# Sheet2.net
KiCad netlist of a schematic drawn in Altium Designer
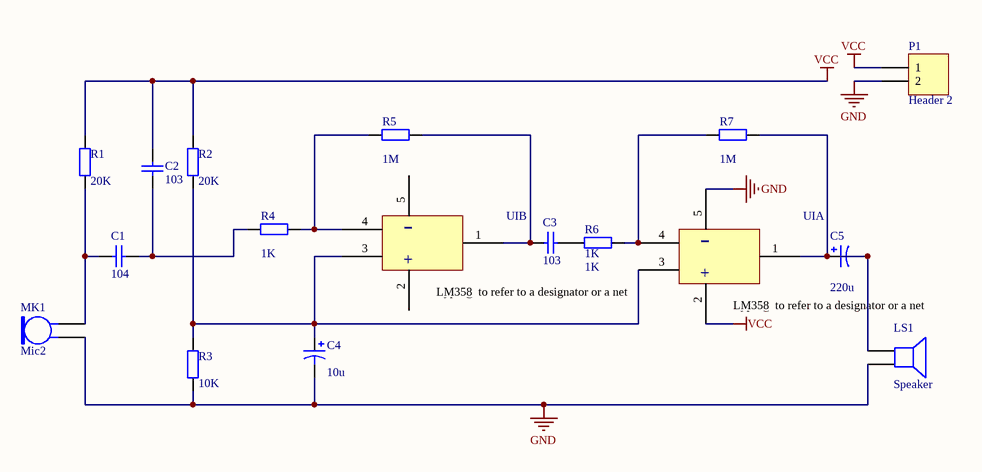
[diagram p0: Sheet2.SchDoc]

(export (version "E")
  (design (tool "Eeschema 10.0.6"))
  (components
    (comp (ref "C1")
      (value "104")
      (footprint "RAD-0.3")
      (description "Capacitor")
      (fields (field (name "PUBLISHER") "Altium Limited"))
      (libsource (lib "Miscellaneous Devices") (part "Cap"))
    )
    (comp (ref "C2")
      (value "103")
      (footprint "RAD-0.3")
      (description "Capacitor")
      (fields (field (name "PUBLISHER") "Altium Limited"))
      (libsource (lib "Miscellaneous Devices") (part "Cap"))
    )
    (comp (ref "C3")
      (value "103")
      (footprint "RAD-0.3")
      (description "Capacitor")
      (fields (field (name "PUBLISHER") "Altium Limited"))
      (libsource (lib "Miscellaneous Devices") (part "Cap"))
    )
    (comp (ref "C4")
      (value "10u")
      (footprint "RB7.6-15")
      (description "Polarized Capacitor (Radial)")
      (fields (field (name "Comment") "Cap Pol1") (field (name "PUBLISHER") "Altium Limited"))
      (libsource (lib "Miscellaneous Devices") (part "Cap Pol1"))
    )
    (comp (ref "C5")
      (value "220u")
      (footprint "RB7.6-15")
      (description "Polarized Capacitor (Radial)")
      (fields (field (name "Comment") "Cap Pol1") (field (name "PUBLISHER") "Altium Limited"))
      (libsource (lib "Miscellaneous Devices") (part "Cap Pol1"))
    )
    (comp (ref "LS1")
      (value "Speaker")
      (footprint "PIN2")
      (description "Loudspeaker")
      (fields (field (name "PUBLISHER") "Altium Limited"))
      (libsource (lib "Miscellaneous Devices") (part "Speaker"))
    )
    (comp (ref "MK1")
      (value "Mic2")
      (footprint "PIN2")
      (description "Microphone")
      (fields (field (name "PUBLISHER") "Altium Limited"))
      (libsource (lib "Miscellaneous Devices") (part "Mic2"))
    )
    (comp (ref "P1")
      (value "Header 2")
      (footprint "HDR1X2")
      (description "Header, 2-Pin")
      (fields (field (name "PUBLISHER") "Altium Limited"))
      (libsource (lib "Miscellaneous Connectors") (part "Header 2"))
    )
    (comp (ref "R1")
      (value "20K")
      (footprint "AXIAL-0.4")
      (description "Resistor")
      (fields (field (name "Comment") "Res2") (field (name "PUBLISHER") "Altium Limited"))
      (libsource (lib "") (part "Res2_1"))
    )
    (comp (ref "R2")
      (value "20K")
      (footprint "AXIAL-0.4")
      (description "Resistor")
      (fields (field (name "Comment") "Res2") (field (name "PUBLISHER") "Altium Limited"))
      (libsource (lib "") (part "Res2_1"))
    )
    (comp (ref "R3")
      (value "10K")
      (footprint "AXIAL-0.4")
      (description "Resistor")
      (fields (field (name "Comment") "Res2") (field (name "PUBLISHER") "Altium Limited"))
      (libsource (lib "") (part "Res2_2"))
    )
    (comp (ref "R4")
      (value "1K")
      (footprint "AXIAL-0.4")
      (description "Resistor")
      (fields (field (name "Comment") "Res2") (field (name "PUBLISHER") "Altium Limited"))
      (libsource (lib "Miscellaneous Devices") (part "Res2"))
    )
    (comp (ref "R5")
      (value "1M")
      (footprint "AXIAL-0.4")
      (description "Resistor")
      (fields (field (name "Comment") "Res2") (field (name "PUBLISHER") "Altium Limited"))
      (libsource (lib "Miscellaneous Devices") (part "Res2"))
    )
    (comp (ref "R6")
      (value "1K")
      (footprint "AXIAL-0.4")
      (description "Resistor")
      (fields (field (name "ALTIUM_VALUE") "1K") (field (name "PUBLISHER") "Altium Limited"))
      (libsource (lib "") (part "Res2_3"))
    )
    (comp (ref "R7")
      (value "1M")
      (footprint "AXIAL-0.4")
      (description "Resistor")
      (fields (field (name "Comment") "Res2") (field (name "PUBLISHER") "Altium Limited"))
      (libsource (lib "") (part "Res2_3"))
    )
    (comp (ref "UIA") (value "双运算放大器") (footprint "LM358") (libsource (lib "1.1Schlib") (part "放大器")))
    (comp (ref "UIB") (value "双运算放大器") (footprint "LM358") (libsource (lib "1.1Schlib") (part "放大器")))
  )
  (nets
    (net (code "1") (name "GND") (class "Default")
      (node (ref "C4") (pin "2") (pinfunction "2_2") (pintype "passive"))
      (node (ref "LS1") (pin "2") (pinfunction "2_2") (pintype "passive"))
      (node (ref "MK1") (pin "1") (pinfunction "1_1") (pintype "passive"))
      (node (ref "P1") (pin "2") (pinfunction "2_2") (pintype "passive"))
      (node (ref "R3") (pin "2") (pinfunction "2_2") (pintype "passive"))
      (node (ref "UIA") (pin "5") (pinfunction "GND_5") (pintype "passive"))
    )
    (net (code "2") (name "Net-(C1-Pad1)") (class "Default")
      (node (ref "C1") (pin "1") (pinfunction "1_1") (pintype "passive"))
      (node (ref "MK1") (pin "2") (pinfunction "2_2") (pintype "passive"))
      (node (ref "R1") (pin "1") (pinfunction "1_1") (pintype "passive"))
    )
    (net (code "3") (name "Net-(C1-Pad2)") (class "Default")
      (node (ref "C1") (pin "2") (pinfunction "2_2") (pintype "passive"))
      (node (ref "C2") (pin "1") (pinfunction "1_1") (pintype "passive"))
      (node (ref "R4") (pin "2") (pinfunction "2_2") (pintype "passive"))
    )
    (net (code "4") (name "Net-(C3-Pad2)") (class "Default")
      (node (ref "C3") (pin "2") (pinfunction "2_2") (pintype "passive"))
      (node (ref "R6") (pin "1") (pinfunction "1_1") (pintype "passive"))
    )
    (net (code "5") (name "Net-(C5-Pad2)") (class "Default")
      (node (ref "C5") (pin "2") (pinfunction "2_2") (pintype "passive"))
      (node (ref "LS1") (pin "1") (pinfunction "1_1") (pintype "passive"))
    )
    (net (code "6") (name "Net-(R4-Pad1)") (class "Default")
      (node (ref "R4") (pin "1") (pinfunction "1_1") (pintype "passive"))
      (node (ref "R5") (pin "2") (pinfunction "2_2") (pintype "passive"))
      (node (ref "UIB") (pin "4") (pintype "passive"))
    )
    (net (code "7") (name "Net-(R6-Pad2)") (class "Default")
      (node (ref "R6") (pin "2") (pinfunction "2_2") (pintype "passive"))
      (node (ref "R7") (pin "1") (pinfunction "1_1") (pintype "passive"))
      (node (ref "UIA") (pin "4") (pintype "passive"))
    )
    (net (code "8") (name "Net-(UIA-21)") (class "Default")
      (node (ref "C5") (pin "1") (pinfunction "1_1") (pintype "passive"))
      (node (ref "R7") (pin "2") (pinfunction "2_2") (pintype "passive"))
      (node (ref "UIA") (pin "1") (pinfunction "21_1") (pintype "passive"))
    )
    (net (code "9") (name "Net-(UIA-24)") (class "Default")
      (node (ref "C4") (pin "1") (pinfunction "1_1") (pintype "passive"))
      (node (ref "R2") (pin "1") (pinfunction "1_1") (pintype "passive"))
      (node (ref "R3") (pin "1") (pinfunction "1_1") (pintype "passive"))
      (node (ref "UIA") (pin "3") (pinfunction "24_3") (pintype "passive"))
      (node (ref "UIB") (pin "3") (pinfunction "24_3") (pintype "passive"))
    )
    (net (code "10") (name "Net-(UIB-21)") (class "Default")
      (node (ref "C3") (pin "1") (pinfunction "1_1") (pintype "passive"))
      (node (ref "R5") (pin "1") (pinfunction "1_1") (pintype "passive"))
      (node (ref "UIB") (pin "1") (pinfunction "21_1") (pintype "passive"))
    )
    (net (code "11") (name "VCC") (class "Default")
      (node (ref "C2") (pin "2") (pinfunction "2_2") (pintype "passive"))
      (node (ref "P1") (pin "1") (pinfunction "1_1") (pintype "passive"))
      (node (ref "R1") (pin "2") (pinfunction "2_2") (pintype "passive"))
      (node (ref "R2") (pin "2") (pinfunction "2_2") (pintype "passive"))
      (node (ref "UIA") (pin "2") (pinfunction "22_2") (pintype "passive"))
    )
    (net (code "12") (name "unconnected-(UIB-22-Pad2)") (class "Default")
      (node (ref "UIB") (pin "2") (pinfunction "22_2") (pintype "passive"))
    )
    (net (code "13") (name "unconnected-(UIB-GND-Pad5)") (class "Default")
      (node (ref "UIB") (pin "5") (pinfunction "GND_5") (pintype "passive"))
    )
  )
)
